# DOIBoard2.net
KiCad netlist of a schematic drawn in Altium Designer
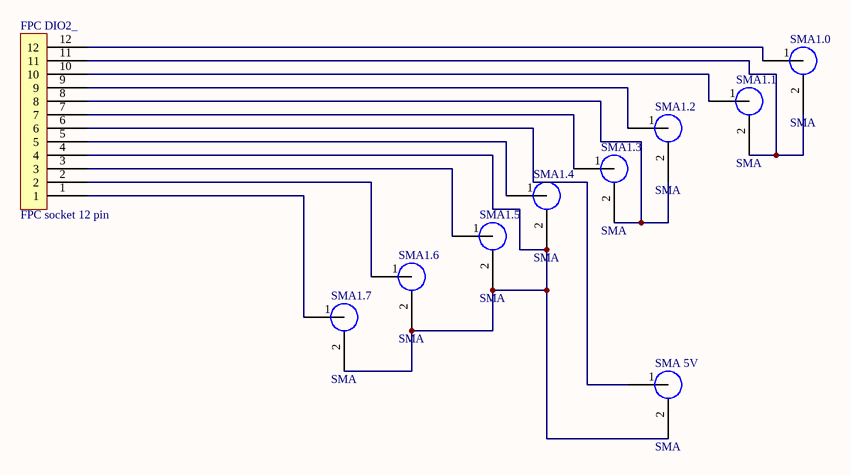
[diagram p0: DOIBoard2.SchDoc]

(export (version "E")
  (design (tool "Eeschema 10.0.6"))
  (components
    (comp (ref "FPC DIO2_")
      (value "FPC socket 12 pin")
      (footprint "FPC 12pin")
      (libsource (lib "Libaray") (part "FPC socket 12 pin"))
    )
    (comp (ref "SMA 5V") (value "SMA") (footprint "SMA") (libsource (lib "Libaray") (part "SMA")))
    (comp (ref "SMA1.0") (value "SMA") (footprint "SMA") (libsource (lib "Libaray") (part "SMA")))
    (comp (ref "SMA1.1") (value "SMA") (footprint "SMA") (libsource (lib "Libaray") (part "SMA")))
    (comp (ref "SMA1.2") (value "SMA") (footprint "SMA") (libsource (lib "Libaray") (part "SMA")))
    (comp (ref "SMA1.3") (value "SMA") (footprint "SMA") (libsource (lib "Libaray") (part "SMA")))
    (comp (ref "SMA1.4") (value "SMA") (footprint "SMA") (libsource (lib "Libaray") (part "SMA")))
    (comp (ref "SMA1.5") (value "SMA") (footprint "SMA") (libsource (lib "Libaray") (part "SMA")))
    (comp (ref "SMA1.6") (value "SMA") (footprint "SMA") (libsource (lib "Libaray") (part "SMA")))
    (comp (ref "SMA1.7") (value "SMA") (footprint "SMA") (libsource (lib "Libaray") (part "SMA")))
  )
  (nets
    (net (code "1") (name "Net-(SMA 5V-Core)") (class "Default")
      (node (ref "FPC DIO2_") (pin "6") (pinfunction "6_6") (pintype "passive"))
      (node (ref "SMA 5V") (pin "1") (pinfunction "Core_1") (pintype "passive"))
    )
    (net (code "2") (name "Net-(SMA 5V-Ground)") (class "Default")
      (node (ref "FPC DIO2_") (pin "4") (pinfunction "4_4") (pintype "passive"))
      (node (ref "SMA 5V") (pin "2") (pinfunction "Ground_2") (pintype "passive"))
      (node (ref "SMA1.4") (pin "2") (pinfunction "Ground_2") (pintype "passive"))
      (node (ref "SMA1.5") (pin "2") (pinfunction "Ground_2") (pintype "passive"))
      (node (ref "SMA1.6") (pin "2") (pinfunction "Ground_2") (pintype "passive"))
      (node (ref "SMA1.7") (pin "2") (pinfunction "Ground_2") (pintype "passive"))
    )
    (net (code "3") (name "Net-(SMA1.0-Core)") (class "Default")
      (node (ref "FPC DIO2_") (pin "12") (pinfunction "12_12") (pintype "passive"))
      (node (ref "SMA1.0") (pin "1") (pinfunction "Core_1") (pintype "passive"))
    )
    (net (code "4") (name "Net-(SMA1.0-Ground)") (class "Default")
      (node (ref "FPC DIO2_") (pin "11") (pinfunction "11_11") (pintype "passive"))
      (node (ref "SMA1.0") (pin "2") (pinfunction "Ground_2") (pintype "passive"))
      (node (ref "SMA1.1") (pin "2") (pinfunction "Ground_2") (pintype "passive"))
    )
    (net (code "5") (name "Net-(SMA1.1-Core)") (class "Default")
      (node (ref "FPC DIO2_") (pin "10") (pinfunction "10_10") (pintype "passive"))
      (node (ref "SMA1.1") (pin "1") (pinfunction "Core_1") (pintype "passive"))
    )
    (net (code "6") (name "Net-(SMA1.2-Core)") (class "Default")
      (node (ref "FPC DIO2_") (pin "9") (pinfunction "9_9") (pintype "passive"))
      (node (ref "SMA1.2") (pin "1") (pinfunction "Core_1") (pintype "passive"))
    )
    (net (code "7") (name "Net-(SMA1.2-Ground)") (class "Default")
      (node (ref "FPC DIO2_") (pin "8") (pinfunction "8_8") (pintype "passive"))
      (node (ref "SMA1.2") (pin "2") (pinfunction "Ground_2") (pintype "passive"))
      (node (ref "SMA1.3") (pin "2") (pinfunction "Ground_2") (pintype "passive"))
    )
    (net (code "8") (name "Net-(SMA1.3-Core)") (class "Default")
      (node (ref "FPC DIO2_") (pin "7") (pinfunction "7_7") (pintype "passive"))
      (node (ref "SMA1.3") (pin "1") (pinfunction "Core_1") (pintype "passive"))
    )
    (net (code "9") (name "Net-(SMA1.4-Core)") (class "Default")
      (node (ref "FPC DIO2_") (pin "5") (pinfunction "5_5") (pintype "passive"))
      (node (ref "SMA1.4") (pin "1") (pinfunction "Core_1") (pintype "passive"))
    )
    (net (code "10") (name "Net-(SMA1.5-Core)") (class "Default")
      (node (ref "FPC DIO2_") (pin "3") (pinfunction "3_3") (pintype "passive"))
      (node (ref "SMA1.5") (pin "1") (pinfunction "Core_1") (pintype "passive"))
    )
    (net (code "11") (name "Net-(SMA1.6-Core)") (class "Default")
      (node (ref "FPC DIO2_") (pin "2") (pinfunction "2_2") (pintype "passive"))
      (node (ref "SMA1.6") (pin "1") (pinfunction "Core_1") (pintype "passive"))
    )
    (net (code "12") (name "Net-(SMA1.7-Core)") (class "Default")
      (node (ref "FPC DIO2_") (pin "1") (pinfunction "1_1") (pintype "passive"))
      (node (ref "SMA1.7") (pin "1") (pinfunction "Core_1") (pintype "passive"))
    )
  )
)
